# CameraInterface.net
KiCad netlist of a schematic drawn in Altium Designer
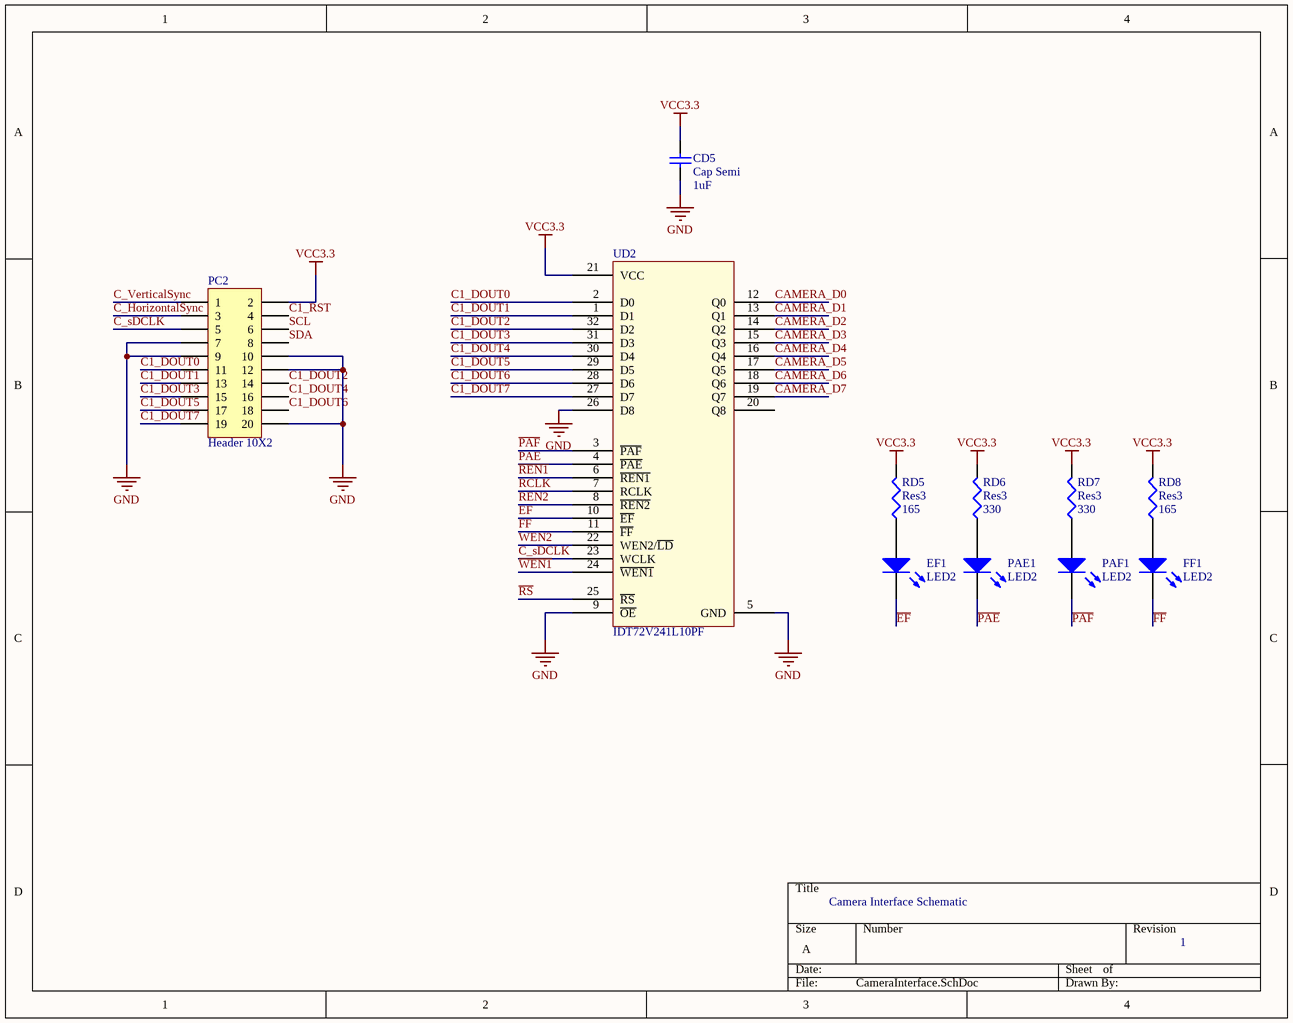
[diagram p0: CameraInterface.SchDoc]

(export (version "E")
  (design (tool "Eeschema 10.0.6"))
  (components
    (comp (ref "CD5")
      (value "Cap Semi")
      (footprint "CAPC1608L")
      (description "Capacitor (Semiconductor SIM Model)")
      (fields (field (name "ALTIUM_VALUE") "1uF") (field (name "PUBLISHER") "Altium Limited"))
      (libsource (lib "Miscellaneous Devices") (part "Cap Semi"))
    )
    (comp (ref "EF1")
      (value "LED2")
      (footprint "DIODE1608")
      (description "Typical RED, GREEN, YELLOW, AMBER GaAs LED")
      (fields (field (name "PUBLISHER") "Altium Limited"))
      (libsource (lib "Miscellaneous Devices") (part "LED2"))
    )
    (comp (ref "FF1")
      (value "LED2")
      (footprint "DIODE1608")
      (description "Typical RED, GREEN, YELLOW, AMBER GaAs LED")
      (fields (field (name "PUBLISHER") "Altium Limited"))
      (libsource (lib "Miscellaneous Devices") (part "LED2"))
    )
    (comp (ref "PAE1")
      (value "LED2")
      (footprint "DIODE1608")
      (description "Typical RED, GREEN, YELLOW, AMBER GaAs LED")
      (fields (field (name "PUBLISHER") "Altium Limited"))
      (libsource (lib "Miscellaneous Devices") (part "LED2"))
    )
    (comp (ref "PAF1")
      (value "LED2")
      (footprint "DIODE1608")
      (description "Typical RED, GREEN, YELLOW, AMBER GaAs LED")
      (fields (field (name "PUBLISHER") "Altium Limited"))
      (libsource (lib "Miscellaneous Devices") (part "LED2"))
    )
    (comp (ref "PC2")
      (value "Header 10X2")
      (footprint "HDR2X10")
      (description "Header, 10-Pin, Dual row")
      (fields (field (name "PUBLISHER") "Altium Limited"))
      (libsource (lib "Miscellaneous Connectors") (part "Header 10X2"))
    )
    (comp (ref "RD5")
      (value "Res3")
      (footprint "RESC1608L")
      (description "Resistor")
      (fields (field (name "ALTIUM_VALUE") "165") (field (name "PUBLISHER") "Altium Limited"))
      (libsource (lib "Miscellaneous Devices") (part "Res3"))
    )
    (comp (ref "RD6")
      (value "Res3")
      (footprint "RESC1608L")
      (description "Resistor")
      (fields (field (name "ALTIUM_VALUE") "330") (field (name "PUBLISHER") "Altium Limited"))
      (libsource (lib "Miscellaneous Devices") (part "Res3"))
    )
    (comp (ref "RD7")
      (value "Res3")
      (footprint "RESC1608L")
      (description "Resistor")
      (fields (field (name "ALTIUM_VALUE") "330") (field (name "PUBLISHER") "Altium Limited"))
      (libsource (lib "Miscellaneous Devices") (part "Res3"))
    )
    (comp (ref "RD8")
      (value "Res3")
      (footprint "RESC1608L")
      (description "Resistor")
      (fields (field (name "ALTIUM_VALUE") "165") (field (name "PUBLISHER") "Altium Limited"))
      (libsource (lib "Miscellaneous Devices") (part "Res3"))
    )
    (comp (ref "UD2")
      (value "IDT72V241L10PF")
      (footprint "IDT72V241L10PF")
      (description "36K (4K x 9) FIFO Buffer")
      (libsource (lib "daughterboard") (part "IDT72V241L10PF"))
    )
  )
  (nets
    (net (code "1") (name "/C1_DOUT0") (class "Default")
      (node (ref "PC2") (pin "11") (pinfunction "11_11") (pintype "passive"))
      (node (ref "UD2") (pin "2") (pinfunction "D0_2") (pintype "passive"))
    )
    (net (code "2") (name "/C1_DOUT1") (class "Default")
      (node (ref "PC2") (pin "13") (pinfunction "13_13") (pintype "passive"))
      (node (ref "UD2") (pin "1") (pinfunction "D1_1") (pintype "passive"))
    )
    (net (code "3") (name "/C1_DOUT2") (class "Default")
      (node (ref "PC2") (pin "14") (pinfunction "14_14") (pintype "passive"))
      (node (ref "UD2") (pin "32") (pinfunction "D2_32") (pintype "passive"))
    )
    (net (code "4") (name "/C1_DOUT3") (class "Default")
      (node (ref "PC2") (pin "15") (pinfunction "15_15") (pintype "passive"))
      (node (ref "UD2") (pin "31") (pinfunction "D3_31") (pintype "passive"))
    )
    (net (code "5") (name "/C1_DOUT4") (class "Default")
      (node (ref "PC2") (pin "16") (pinfunction "16_16") (pintype "passive"))
      (node (ref "UD2") (pin "30") (pinfunction "D4_30") (pintype "passive"))
    )
    (net (code "6") (name "/C1_DOUT5") (class "Default")
      (node (ref "PC2") (pin "17") (pinfunction "17_17") (pintype "passive"))
      (node (ref "UD2") (pin "29") (pinfunction "D5_29") (pintype "passive"))
    )
    (net (code "7") (name "/C1_DOUT6") (class "Default")
      (node (ref "PC2") (pin "18") (pinfunction "18_18") (pintype "passive"))
      (node (ref "UD2") (pin "28") (pinfunction "D6_28") (pintype "passive"))
    )
    (net (code "8") (name "/C1_DOUT7") (class "Default")
      (node (ref "PC2") (pin "19") (pinfunction "19_19") (pintype "passive"))
      (node (ref "UD2") (pin "27") (pinfunction "D7_27") (pintype "passive"))
    )
    (net (code "9") (name "/C1_RST") (class "Default")
      (node (ref "PC2") (pin "4") (pinfunction "4_4") (pintype "passive"))
    )
    (net (code "10") (name "/CAMERA_D0") (class "Default")
      (node (ref "UD2") (pin "12") (pinfunction "Q0_12") (pintype "passive"))
    )
    (net (code "11") (name "/CAMERA_D1") (class "Default")
      (node (ref "UD2") (pin "13") (pinfunction "Q1_13") (pintype "passive"))
    )
    (net (code "12") (name "/CAMERA_D2") (class "Default")
      (node (ref "UD2") (pin "14") (pinfunction "Q2_14") (pintype "passive"))
    )
    (net (code "13") (name "/CAMERA_D3") (class "Default")
      (node (ref "UD2") (pin "15") (pinfunction "Q3_15") (pintype "passive"))
    )
    (net (code "14") (name "/CAMERA_D4") (class "Default")
      (node (ref "UD2") (pin "16") (pinfunction "Q4_16") (pintype "passive"))
    )
    (net (code "15") (name "/CAMERA_D5") (class "Default")
      (node (ref "UD2") (pin "17") (pinfunction "Q5_17") (pintype "passive"))
    )
    (net (code "16") (name "/CAMERA_D6") (class "Default")
      (node (ref "UD2") (pin "18") (pinfunction "Q6_18") (pintype "passive"))
    )
    (net (code "17") (name "/CAMERA_D7") (class "Default")
      (node (ref "UD2") (pin "19") (pinfunction "Q7_19") (pintype "passive"))
    )
    (net (code "18") (name "/C_HorizontalSync") (class "Default")
      (node (ref "PC2") (pin "3") (pinfunction "3_3") (pintype "passive"))
    )
    (net (code "19") (name "/C_VerticalSync") (class "Default")
      (node (ref "PC2") (pin "1") (pinfunction "1_1") (pintype "passive"))
    )
    (net (code "20") (name "/C_sDCLK") (class "Default")
      (node (ref "PC2") (pin "5") (pinfunction "5_5") (pintype "passive"))
      (node (ref "UD2") (pin "23") (pinfunction "WCLK_23") (pintype "passive"))
    )
    (net (code "21") (name "/RCLK") (class "Default")
      (node (ref "UD2") (pin "7") (pinfunction "RCLK_7") (pintype "passive"))
    )
    (net (code "22") (name "/SCL") (class "Default")
      (node (ref "PC2") (pin "6") (pinfunction "6_6") (pintype "passive"))
    )
    (net (code "23") (name "/SDA") (class "Default")
      (node (ref "PC2") (pin "8") (pinfunction "8_8") (pintype "passive"))
    )
    (net (code "24") (name "/WEN2") (class "Default")
      (node (ref "UD2") (pin "22") (pinfunction "WEN2/~{LD}_22") (pintype "passive"))
    )
    (net (code "25") (name "/~{EF}") (class "Default")
      (node (ref "EF1") (pin "2") (pinfunction "K_2") (pintype "passive"))
      (node (ref "UD2") (pin "10") (pinfunction "~{EF}_10") (pintype "passive"))
    )
    (net (code "26") (name "/~{FF}") (class "Default")
      (node (ref "FF1") (pin "2") (pinfunction "K_2") (pintype "passive"))
      (node (ref "UD2") (pin "11") (pinfunction "~{FF}_11") (pintype "passive"))
    )
    (net (code "27") (name "/~{PAE}") (class "Default")
      (node (ref "PAE1") (pin "2") (pinfunction "K_2") (pintype "passive"))
      (node (ref "UD2") (pin "4") (pinfunction "~{PAE}_4") (pintype "passive"))
    )
    (net (code "28") (name "/~{PAF}") (class "Default")
      (node (ref "PAF1") (pin "2") (pinfunction "K_2") (pintype "passive"))
      (node (ref "UD2") (pin "3") (pinfunction "~{PAF}_3") (pintype "passive"))
    )
    (net (code "29") (name "/~{REN1}") (class "Default")
      (node (ref "UD2") (pin "6") (pinfunction "~{REN1}_6") (pintype "passive"))
    )
    (net (code "30") (name "/~{REN2}") (class "Default")
      (node (ref "UD2") (pin "8") (pinfunction "~{REN2}_8") (pintype "passive"))
    )
    (net (code "31") (name "/~{RS}") (class "Default")
      (node (ref "UD2") (pin "25") (pinfunction "~{RS}_25") (pintype "passive"))
    )
    (net (code "32") (name "/~{WEN1}") (class "Default")
      (node (ref "UD2") (pin "24") (pinfunction "~{WEN1}_24") (pintype "passive"))
    )
    (net (code "33") (name "GND") (class "Default")
      (node (ref "CD5") (pin "1") (pinfunction "1_1") (pintype "passive"))
      (node (ref "PC2") (pin "10") (pinfunction "10_10") (pintype "passive"))
      (node (ref "PC2") (pin "12") (pinfunction "12_12") (pintype "passive"))
      (node (ref "PC2") (pin "20") (pinfunction "20_20") (pintype "passive"))
      (node (ref "PC2") (pin "7") (pinfunction "7_7") (pintype "passive"))
      (node (ref "PC2") (pin "9") (pinfunction "9_9") (pintype "passive"))
      (node (ref "UD2") (pin "26") (pinfunction "D8_26") (pintype "passive"))
      (node (ref "UD2") (pin "5") (pinfunction "GND_5") (pintype "passive"))
      (node (ref "UD2") (pin "9") (pinfunction "~{OE}_9") (pintype "passive"))
    )
    (net (code "34") (name "Net-(EF1-A)") (class "Default")
      (node (ref "EF1") (pin "1") (pinfunction "A_1") (pintype "passive"))
      (node (ref "RD5") (pin "1") (pinfunction "1_1") (pintype "passive"))
    )
    (net (code "35") (name "Net-(FF1-A)") (class "Default")
      (node (ref "FF1") (pin "1") (pinfunction "A_1") (pintype "passive"))
      (node (ref "RD8") (pin "1") (pinfunction "1_1") (pintype "passive"))
    )
    (net (code "36") (name "Net-(PAE1-A)") (class "Default")
      (node (ref "PAE1") (pin "1") (pinfunction "A_1") (pintype "passive"))
      (node (ref "RD6") (pin "1") (pinfunction "1_1") (pintype "passive"))
    )
    (net (code "37") (name "Net-(PAF1-A)") (class "Default")
      (node (ref "PAF1") (pin "1") (pinfunction "A_1") (pintype "passive"))
      (node (ref "RD7") (pin "1") (pinfunction "1_1") (pintype "passive"))
    )
    (net (code "38") (name "VCC3.3") (class "Default")
      (node (ref "CD5") (pin "2") (pinfunction "2_2") (pintype "passive"))
      (node (ref "PC2") (pin "2") (pinfunction "2_2") (pintype "passive"))
      (node (ref "RD5") (pin "2") (pinfunction "2_2") (pintype "passive"))
      (node (ref "RD6") (pin "2") (pinfunction "2_2") (pintype "passive"))
      (node (ref "RD7") (pin "2") (pinfunction "2_2") (pintype "passive"))
      (node (ref "RD8") (pin "2") (pinfunction "2_2") (pintype "passive"))
      (node (ref "UD2") (pin "21") (pinfunction "VCC_21") (pintype "passive"))
    )
    (net (code "39") (name "unconnected-(UD2-Q8-Pad20)") (class "Default")
      (node (ref "UD2") (pin "20") (pinfunction "Q8_20") (pintype "passive"))
    )
  )
)
